# testing.net
KiCad netlist of a schematic drawn in EAGLE
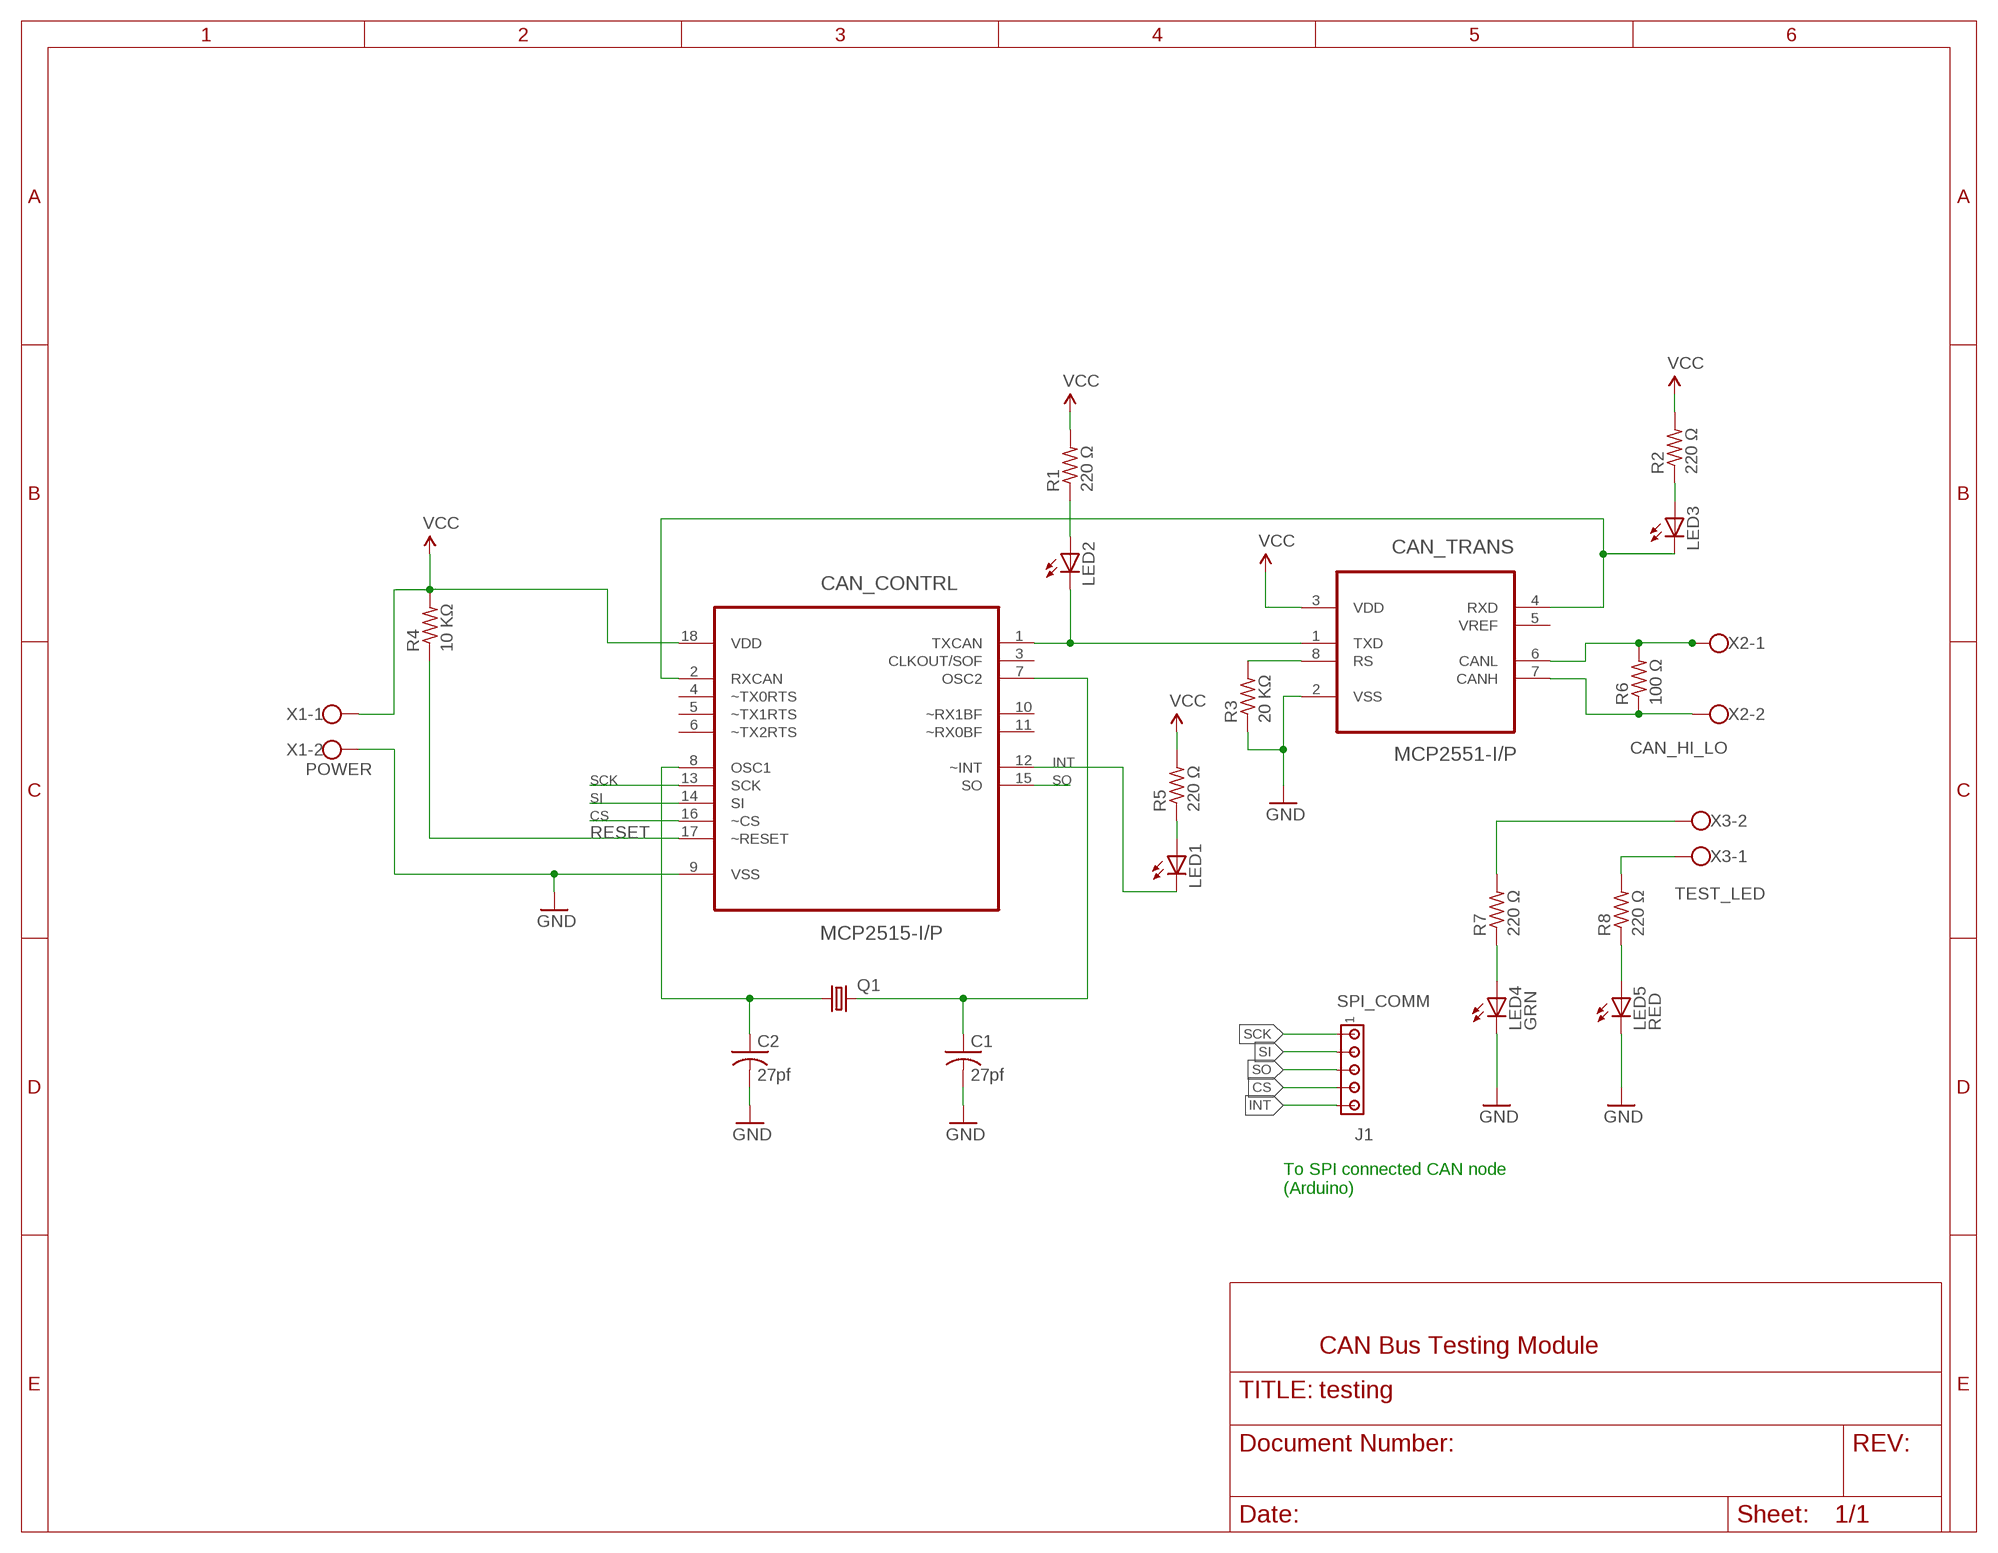
[diagram p0: schematic, sheet 1]

(export (version "E")
  (design (tool "Eeschema 10.0.6"))
  (components
    (comp (ref "C1")
      (value "27pf")
      (footprint "eagle-import:C025-040X050")
      (libsource (lib "eagle-import") (part "C-US025-040X050"))
    )
    (comp (ref "C2")
      (value "27pf")
      (footprint "eagle-import:C025-040X050")
      (libsource (lib "eagle-import") (part "C-US025-040X050"))
    )
    (comp (ref "CAN_CONTRL")
      (value "MCP2515-I/P")
      (footprint "eagle-import:DIP254P762X432-18")
      (libsource (lib "eagle-import") (part "MCP2515-I/P"))
    )
    (comp (ref "CAN_TRANS")
      (value "MCP2551-I/P")
      (footprint "eagle-import:DIP254P762X432-8")
      (libsource (lib "eagle-import") (part "MCP2551-I/P"))
    )
    (comp (ref "J1")
      (value "SPI_COMM")
      (footprint "eagle-import:1X5MTA")
      (libsource (lib "eagle-import") (part "MTA05-156"))
    )
    (comp (ref "LED1")
      (value "LED5MM")
      (footprint "eagle-import:LED5MM")
      (libsource (lib "eagle-import") (part "LED5MM"))
    )
    (comp (ref "LED2")
      (value "LED5MM")
      (footprint "eagle-import:LED5MM")
      (libsource (lib "eagle-import") (part "LED5MM"))
    )
    (comp (ref "LED3")
      (value "LED5MM")
      (footprint "eagle-import:LED5MM")
      (libsource (lib "eagle-import") (part "LED5MM"))
    )
    (comp (ref "LED4")
      (value "GRN")
      (footprint "eagle-import:LED5MM")
      (libsource (lib "eagle-import") (part "LED5MM"))
    )
    (comp (ref "LED5")
      (value "RED")
      (footprint "eagle-import:LED5MM")
      (libsource (lib "eagle-import") (part "LED5MM"))
    )
    (comp (ref "Q1")
      (value "CRYTALHC18U-V")
      (footprint "eagle-import:HC18U-V")
      (libsource (lib "eagle-import") (part "CRYTALHC18U-V"))
    )
    (comp (ref "R1")
      (value "220 Ω")
      (footprint "eagle-import:0204_7")
      (libsource (lib "eagle-import") (part "R-US_0204/7"))
    )
    (comp (ref "R2")
      (value "220 Ω")
      (footprint "eagle-import:0204_7")
      (libsource (lib "eagle-import") (part "R-US_0204/7"))
    )
    (comp (ref "R3")
      (value "20 KΩ")
      (footprint "eagle-import:0204_7")
      (libsource (lib "eagle-import") (part "R-US_0204/7"))
    )
    (comp (ref "R4")
      (value "10 KΩ")
      (footprint "eagle-import:0204_7")
      (libsource (lib "eagle-import") (part "R-US_0204/7"))
    )
    (comp (ref "R5")
      (value "220 Ω")
      (footprint "eagle-import:0204_7")
      (libsource (lib "eagle-import") (part "R-US_0204/7"))
    )
    (comp (ref "R6")
      (value "100 Ω")
      (footprint "eagle-import:0204_7")
      (libsource (lib "eagle-import") (part "R-US_0204/7"))
    )
    (comp (ref "R7")
      (value "220 Ω")
      (footprint "eagle-import:0204_7")
      (libsource (lib "eagle-import") (part "R-US_0204/7"))
    )
    (comp (ref "R8")
      (value "220 Ω")
      (footprint "eagle-import:0204_7")
      (libsource (lib "eagle-import") (part "R-US_0204/7"))
    )
    (comp (ref "X1")
      (value "POWER")
      (footprint "eagle-import:W237-102")
      (fields (field (name "MPN") "237-102"))
      (libsource (lib "eagle-import") (part "W237-102"))
    )
    (comp (ref "X2")
      (value "CAN_HI_LO")
      (footprint "eagle-import:W237-102")
      (fields (field (name "MPN") "237-102"))
      (libsource (lib "eagle-import") (part "W237-102"))
    )
    (comp (ref "X3")
      (value "TEST_LED")
      (footprint "eagle-import:W237-102")
      (fields (field (name "MPN") "237-102"))
      (libsource (lib "eagle-import") (part "W237-102"))
    )
  )
  (nets
    (net (code "1") (name "/RESET") (class "Default")
      (node (ref "CAN_CONTRL") (pin "17") (pinfunction "~{RESET}_17") (pintype "input"))
      (node (ref "R4") (pin "1") (pinfunction "1_1") (pintype "passive"))
    )
    (net (code "2") (name "CS") (class "Default")
      (node (ref "CAN_CONTRL") (pin "16") (pinfunction "~{CS}_16") (pintype "input"))
      (node (ref "J1") (pin "4") (pinfunction "4_4") (pintype "passive"))
    )
    (net (code "3") (name "GND") (class "Default")
      (node (ref "C1") (pin "2") (pinfunction "2_2") (pintype "passive"))
      (node (ref "C2") (pin "2") (pinfunction "2_2") (pintype "passive"))
      (node (ref "CAN_CONTRL") (pin "9") (pinfunction "VSS_9") (pintype "power_in"))
      (node (ref "CAN_TRANS") (pin "2") (pinfunction "VSS_2") (pintype "power_in"))
      (node (ref "LED4") (pin "K") (pinfunction "C_K") (pintype "passive"))
      (node (ref "LED5") (pin "K") (pinfunction "C_K") (pintype "passive"))
      (node (ref "R3") (pin "1") (pinfunction "1_1") (pintype "passive"))
      (node (ref "X1") (pin "2") (pinfunction "KL_2") (pintype "passive"))
    )
    (net (code "4") (name "INT") (class "Default")
      (node (ref "CAN_CONTRL") (pin "12") (pinfunction "~{INT}_12") (pintype "output"))
      (node (ref "J1") (pin "5") (pinfunction "5_5") (pintype "passive"))
      (node (ref "LED1") (pin "K") (pinfunction "C_K") (pintype "passive"))
    )
    (net (code "5") (name "Net-(CAN_CONTRL-OSC1)") (class "Default")
      (node (ref "C2") (pin "1") (pinfunction "1_1") (pintype "passive"))
      (node (ref "CAN_CONTRL") (pin "8") (pinfunction "OSC1_8") (pintype "input"))
      (node (ref "Q1") (pin "1") (pinfunction "1_1") (pintype "passive"))
    )
    (net (code "6") (name "Net-(CAN_CONTRL-OSC2)") (class "Default")
      (node (ref "C1") (pin "1") (pinfunction "1_1") (pintype "passive"))
      (node (ref "CAN_CONTRL") (pin "7") (pinfunction "OSC2_7") (pintype "output"))
      (node (ref "Q1") (pin "2") (pinfunction "2_2") (pintype "passive"))
    )
    (net (code "7") (name "Net-(CAN_CONTRL-RXCAN)") (class "Default")
      (node (ref "CAN_CONTRL") (pin "2") (pinfunction "RXCAN_2") (pintype "input"))
      (node (ref "CAN_TRANS") (pin "4") (pinfunction "RXD_4") (pintype "output"))
      (node (ref "LED3") (pin "K") (pinfunction "C_K") (pintype "passive"))
    )
    (net (code "8") (name "Net-(CAN_CONTRL-TXCAN)") (class "Default")
      (node (ref "CAN_CONTRL") (pin "1") (pinfunction "TXCAN_1") (pintype "output"))
      (node (ref "CAN_TRANS") (pin "1") (pinfunction "TXD_1") (pintype "input"))
      (node (ref "LED2") (pin "K") (pinfunction "C_K") (pintype "passive"))
    )
    (net (code "9") (name "Net-(CAN_TRANS-CANH)") (class "Default")
      (node (ref "CAN_TRANS") (pin "7") (pinfunction "CANH_7") (pintype "bidirectional"))
      (node (ref "R6") (pin "1") (pinfunction "1_1") (pintype "passive"))
      (node (ref "X2") (pin "2") (pinfunction "KL_2") (pintype "passive"))
    )
    (net (code "10") (name "Net-(CAN_TRANS-CANL)") (class "Default")
      (node (ref "CAN_TRANS") (pin "6") (pinfunction "CANL_6") (pintype "bidirectional"))
      (node (ref "R6") (pin "2") (pinfunction "2_2") (pintype "passive"))
      (node (ref "X2") (pin "1") (pinfunction "KL_1") (pintype "passive"))
    )
    (net (code "11") (name "Net-(CAN_TRANS-RS)") (class "Default")
      (node (ref "CAN_TRANS") (pin "8") (pinfunction "RS_8") (pintype "input"))
      (node (ref "R3") (pin "2") (pinfunction "2_2") (pintype "passive"))
    )
    (net (code "12") (name "Net-(LED1-PadA)") (class "Default")
      (node (ref "LED1") (pin "A") (pinfunction "A_A") (pintype "passive"))
      (node (ref "R5") (pin "1") (pinfunction "1_1") (pintype "passive"))
    )
    (net (code "13") (name "Net-(LED2-PadA)") (class "Default")
      (node (ref "LED2") (pin "A") (pinfunction "A_A") (pintype "passive"))
      (node (ref "R1") (pin "1") (pinfunction "1_1") (pintype "passive"))
    )
    (net (code "14") (name "Net-(LED3-PadA)") (class "Default")
      (node (ref "LED3") (pin "A") (pinfunction "A_A") (pintype "passive"))
      (node (ref "R2") (pin "1") (pinfunction "1_1") (pintype "passive"))
    )
    (net (code "15") (name "Net-(LED4-PadA)") (class "Default")
      (node (ref "LED4") (pin "A") (pinfunction "A_A") (pintype "passive"))
      (node (ref "R7") (pin "1") (pinfunction "1_1") (pintype "passive"))
    )
    (net (code "16") (name "Net-(LED5-PadA)") (class "Default")
      (node (ref "LED5") (pin "A") (pinfunction "A_A") (pintype "passive"))
      (node (ref "R8") (pin "1") (pinfunction "1_1") (pintype "passive"))
    )
    (net (code "17") (name "Net-(X3A-KL)") (class "Default")
      (node (ref "R8") (pin "2") (pinfunction "2_2") (pintype "passive"))
      (node (ref "X3") (pin "1") (pinfunction "KL_1") (pintype "passive"))
    )
    (net (code "18") (name "Net-(X3B-KL)") (class "Default")
      (node (ref "R7") (pin "2") (pinfunction "2_2") (pintype "passive"))
      (node (ref "X3") (pin "2") (pinfunction "KL_2") (pintype "passive"))
    )
    (net (code "19") (name "SCK") (class "Default")
      (node (ref "CAN_CONTRL") (pin "13") (pinfunction "SCK_13") (pintype "input"))
      (node (ref "J1") (pin "1") (pinfunction "1_1") (pintype "passive"))
    )
    (net (code "20") (name "SI") (class "Default")
      (node (ref "CAN_CONTRL") (pin "14") (pinfunction "SI_14") (pintype "input"))
      (node (ref "J1") (pin "2") (pinfunction "2_2") (pintype "passive"))
    )
    (net (code "21") (name "SO") (class "Default")
      (node (ref "CAN_CONTRL") (pin "15") (pinfunction "SO_15") (pintype "output"))
      (node (ref "J1") (pin "3") (pinfunction "3_3") (pintype "passive"))
    )
    (net (code "22") (name "VCC") (class "Default")
      (node (ref "CAN_CONTRL") (pin "18") (pinfunction "VDD_18") (pintype "power_in"))
      (node (ref "CAN_TRANS") (pin "3") (pinfunction "VDD_3") (pintype "power_in"))
      (node (ref "R1") (pin "2") (pinfunction "2_2") (pintype "passive"))
      (node (ref "R2") (pin "2") (pinfunction "2_2") (pintype "passive"))
      (node (ref "R4") (pin "2") (pinfunction "2_2") (pintype "passive"))
      (node (ref "R5") (pin "2") (pinfunction "2_2") (pintype "passive"))
      (node (ref "X1") (pin "1") (pinfunction "KL_1") (pintype "passive"))
    )
    (net (code "23") (name "unconnected-(CAN_CONTRL-CLKOUT{slash}SOF-Pad3)") (class "Default")
      (node (ref "CAN_CONTRL") (pin "3") (pinfunction "CLKOUT/SOF_3") (pintype "output"))
    )
    (net (code "24") (name "unconnected-(CAN_CONTRL-~{RX0BF}-Pad11)") (class "Default")
      (node (ref "CAN_CONTRL") (pin "11") (pinfunction "~{RX0BF}_11") (pintype "output"))
    )
    (net (code "25") (name "unconnected-(CAN_CONTRL-~{RX1BF}-Pad10)") (class "Default")
      (node (ref "CAN_CONTRL") (pin "10") (pinfunction "~{RX1BF}_10") (pintype "output"))
    )
    (net (code "26") (name "unconnected-(CAN_CONTRL-~{TX0RTS}-Pad4)") (class "Default")
      (node (ref "CAN_CONTRL") (pin "4") (pinfunction "~{TX0RTS}_4") (pintype "input"))
    )
    (net (code "27") (name "unconnected-(CAN_CONTRL-~{TX1RTS}-Pad5)") (class "Default")
      (node (ref "CAN_CONTRL") (pin "5") (pinfunction "~{TX1RTS}_5") (pintype "input"))
    )
    (net (code "28") (name "unconnected-(CAN_CONTRL-~{TX2RTS}-Pad6)") (class "Default")
      (node (ref "CAN_CONTRL") (pin "6") (pinfunction "~{TX2RTS}_6") (pintype "input"))
    )
    (net (code "29") (name "unconnected-(CAN_TRANS-VREF-Pad5)") (class "Default")
      (node (ref "CAN_TRANS") (pin "5") (pinfunction "VREF_5") (pintype "output"))
    )
  )
)
